# qspi_flash.net
KiCad netlist of a schematic drawn in Altium Designer
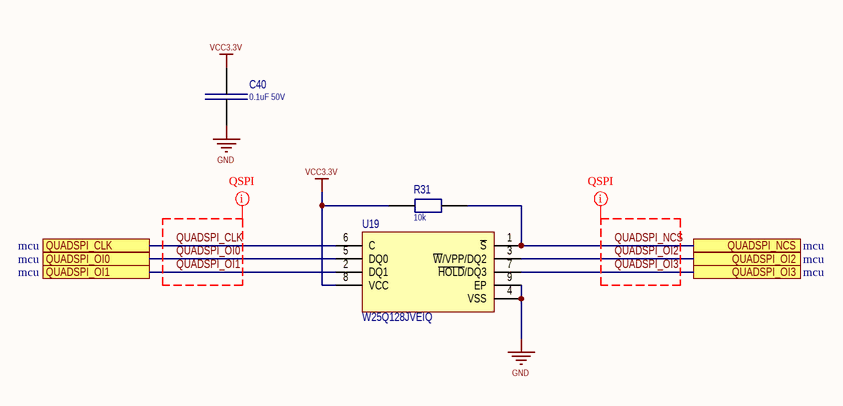
[diagram p0: qspi_flash.schdoc]

(export (version "E")
  (design (tool "Eeschema 10.0.6"))
  (components
    (comp (ref "C40")
      (value "0.1uF 50V")
      (footprint "C_0603")
      (description "Capacitor")
      (fields (field (name "PART") "CC0603KPX7R9BB104"))
      (libsource (lib "AX_Altium_v2.3") (part "C0603"))
    )
    (comp (ref "R31")
      (value "10k")
      (footprint "R_0603")
      (description "Resistor")
      (fields (field (name "PART") "RC0603FR-0710KL"))
      (libsource (lib "resistors") (part "RES_SMD"))
    )
    (comp (ref "U19")
      (value "W25Q128JVEIQ")
      (footprint "W-PDFN-8 (MLP8) – 8mm ? 6mm  Se")
      (description "Flash Memory")
      (libsource (lib "AX_Altium_v2.3") (part "MT25QL********W9-0SIT"))
    )
  )
  (nets
    (net (code "1") (name "/QUADSPI_CLK") (class "Default")
      (node (ref "U19") (pin "6") (pinfunction "C_6") (pintype "passive"))
    )
    (net (code "2") (name "/QUADSPI_NCS") (class "Default")
      (node (ref "R31") (pin "2") (pinfunction "2_2") (pintype "passive"))
      (node (ref "U19") (pin "1") (pinfunction "~{S}_1") (pintype "passive"))
    )
    (net (code "3") (name "/QUADSPI_OI0") (class "Default")
      (node (ref "U19") (pin "5") (pinfunction "DQ0_5") (pintype "passive"))
    )
    (net (code "4") (name "/QUADSPI_OI1") (class "Default")
      (node (ref "U19") (pin "2") (pinfunction "DQ1_2") (pintype "passive"))
    )
    (net (code "5") (name "/QUADSPI_OI2") (class "Default")
      (node (ref "U19") (pin "3") (pinfunction "~{W}/VPP/DQ2_3") (pintype "passive"))
    )
    (net (code "6") (name "/QUADSPI_OI3") (class "Default")
      (node (ref "U19") (pin "7") (pinfunction "~{HOLD}/DQ3_7") (pintype "passive"))
    )
    (net (code "7") (name "GND") (class "Default")
      (node (ref "C40") (pin "1") (pinfunction "1_1") (pintype "passive"))
      (node (ref "U19") (pin "4") (pinfunction "VSS_4") (pintype "passive"))
      (node (ref "U19") (pin "9") (pinfunction "EP_9") (pintype "passive"))
    )
    (net (code "8") (name "VCC3.3V") (class "Default")
      (node (ref "C40") (pin "2") (pinfunction "2_2") (pintype "passive"))
      (node (ref "R31") (pin "1") (pinfunction "1_1") (pintype "passive"))
      (node (ref "U19") (pin "8") (pinfunction "VCC_8") (pintype "passive"))
    )
  )
)
